# esp32_cam_rev_B.net
KiCad netlist of a schematic drawn in EAGLE
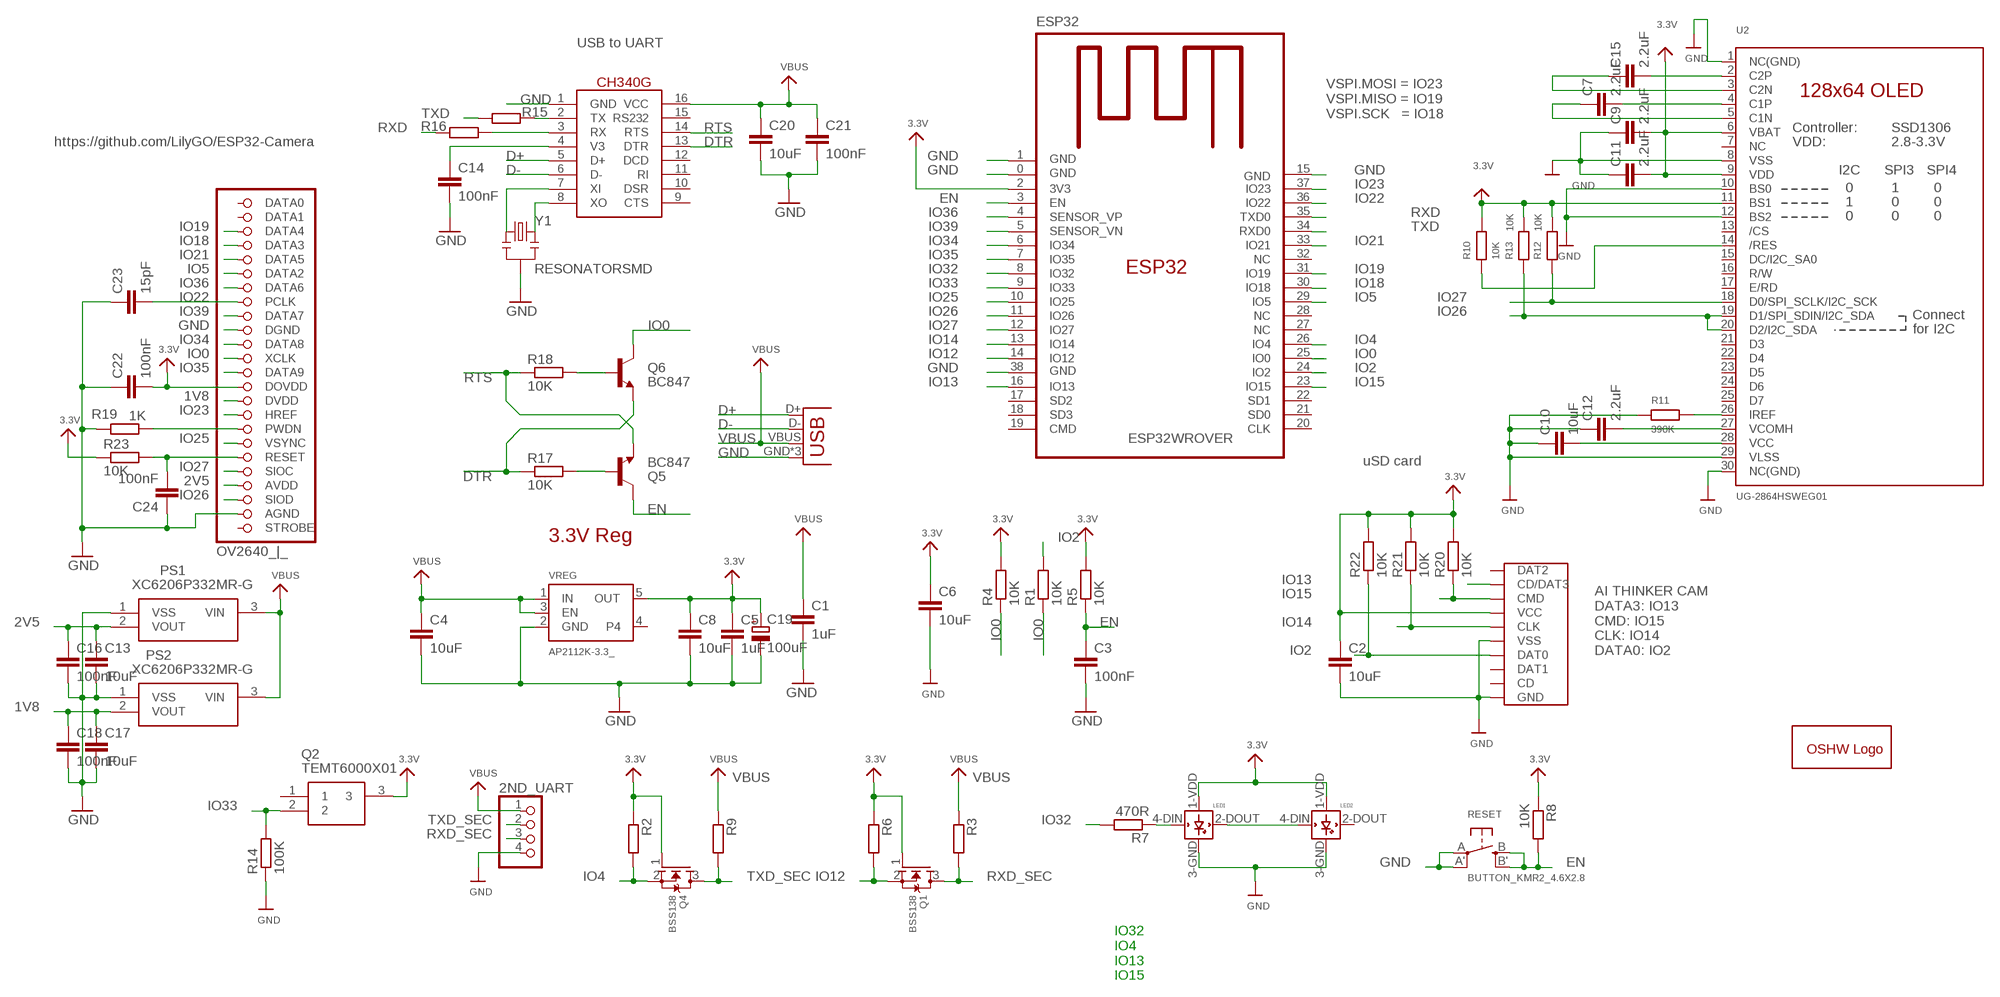
[diagram p0: schematic, sheet 1]

(export (version "E")
  (design (tool "Eeschema 10.0.6"))
  (components
    (comp (ref "2ND_UART")
      (value "JST_PH4")
      (footprint "eagle-import:JSTPH4")
      (libsource (lib "eagle-import") (part "JST_PH4"))
    )
    (comp (ref "C1")
      (value "1uF")
      (footprint "eagle-import:C0805K")
      (libsource (lib "eagle-import") (part "C-EUC0805K"))
    )
    (comp (ref "C2")
      (value "10uF")
      (footprint "eagle-import:C0805")
      (libsource (lib "eagle-import") (part "C-EUC0805"))
    )
    (comp (ref "C3")
      (value "100nF")
      (footprint "eagle-import:C0805K")
      (libsource (lib "eagle-import") (part "C-EUC0805K"))
    )
    (comp (ref "C4")
      (value "10uF")
      (footprint "eagle-import:C0805")
      (libsource (lib "eagle-import") (part "C-EUC0805"))
    )
    (comp (ref "C5")
      (value "1uF")
      (footprint "eagle-import:C0805")
      (libsource (lib "eagle-import") (part "C-EUC0805"))
    )
    (comp (ref "C6")
      (value "10uF")
      (footprint "eagle-import:C0805K")
      (libsource (lib "eagle-import") (part "C-EUC0805K"))
    )
    (comp (ref "C7")
      (value "2.2uF")
      (footprint "eagle-import:C0805")
      (libsource (lib "eagle-import") (part "C-EUC0805"))
    )
    (comp (ref "C8")
      (value "10uF")
      (footprint "eagle-import:C0805")
      (libsource (lib "eagle-import") (part "C-EUC0805"))
    )
    (comp (ref "C9")
      (value "2.2uF")
      (footprint "eagle-import:C0805")
      (libsource (lib "eagle-import") (part "C-EUC0805"))
    )
    (comp (ref "C10")
      (value "10uF")
      (footprint "eagle-import:C0805")
      (libsource (lib "eagle-import") (part "C-EUC0805"))
    )
    (comp (ref "C11")
      (value "2.2uF")
      (footprint "eagle-import:C0805")
      (libsource (lib "eagle-import") (part "C-EUC0805"))
    )
    (comp (ref "C12")
      (value "2.2uF")
      (footprint "eagle-import:C0805")
      (libsource (lib "eagle-import") (part "C-EUC0805"))
    )
    (comp (ref "C13")
      (value "10uF")
      (footprint "eagle-import:C0805")
      (libsource (lib "eagle-import") (part "C-EUC0805"))
    )
    (comp (ref "C14")
      (value "100nF")
      (footprint "eagle-import:C0805K")
      (libsource (lib "eagle-import") (part "C-EUC0805K"))
    )
    (comp (ref "C15")
      (value "2.2uF")
      (footprint "eagle-import:C0805")
      (libsource (lib "eagle-import") (part "C-EUC0805"))
    )
    (comp (ref "C16")
      (value "100nF")
      (footprint "eagle-import:C0805")
      (libsource (lib "eagle-import") (part "C-EUC0805"))
    )
    (comp (ref "C17")
      (value "10uF")
      (footprint "eagle-import:C0805")
      (libsource (lib "eagle-import") (part "C-EUC0805"))
    )
    (comp (ref "C18")
      (value "100nF")
      (footprint "eagle-import:C0805")
      (libsource (lib "eagle-import") (part "C-EUC0805"))
    )
    (comp (ref "C19")
      (value "100uF")
      (footprint "eagle-import:CT6032")
      (libsource (lib "eagle-import") (part "CPOL-EUCT6032"))
    )
    (comp (ref "C20")
      (value "10uF")
      (footprint "eagle-import:C0805")
      (libsource (lib "eagle-import") (part "C-EUC0805"))
    )
    (comp (ref "C21")
      (value "100nF")
      (footprint "eagle-import:C0805")
      (libsource (lib "eagle-import") (part "C-EUC0805"))
    )
    (comp (ref "C22")
      (value "100nF")
      (footprint "eagle-import:C0805")
      (libsource (lib "eagle-import") (part "C-EUC0805"))
    )
    (comp (ref "C23")
      (value "15pF")
      (footprint "eagle-import:C0805")
      (libsource (lib "eagle-import") (part "C-EUC0805"))
    )
    (comp (ref "C24")
      (value "100nF")
      (footprint "eagle-import:C0805")
      (libsource (lib "eagle-import") (part "C-EUC0805"))
    )
    (comp (ref "CH340G")
      (value "CH340G")
      (footprint "eagle-import:SO16")
      (libsource (lib "eagle-import") (part "CH340G"))
    )
    (comp (ref "ESP32")
      (value "ESP32WROVER")
      (footprint "eagle-import:ESP32WROVER")
      (libsource (lib "eagle-import") (part "ESP32WROVER"))
    )
    (comp (ref "FPC_CONNECTOR")
      (value "OV2640_|_")
      (footprint "eagle-import:5051102491")
      (libsource (lib "eagle-import") (part "OV2640_|_"))
    )
    (comp (ref "GOLD_ORB_SM1")
      (value "OSHWLOGO_")
      (footprint "eagle-import:OSHW_5MM_LOGO")
      (libsource (lib "eagle-import") (part "OSHWLOGO_"))
    )
    (comp (ref "LED1")
      (value "WS2812B")
      (footprint "eagle-import:WS2812B_5050")
      (libsource (lib "eagle-import") (part "WS2812B"))
    )
    (comp (ref "LED2")
      (value "WS2812B")
      (footprint "eagle-import:WS2812B_5050")
      (libsource (lib "eagle-import") (part "WS2812B"))
    )
    (comp (ref "PS1")
      (value "XC6206P332MR-G")
      (footprint "eagle-import:SOT95P280X130-3N")
      (fields (field (name "MOUSER_PART_NUMBER") "865-XC6206P332MR-G"))
      (libsource (lib "eagle-import") (part "XC6206P332MR-G"))
    )
    (comp (ref "PS2")
      (value "XC6206P332MR-G")
      (footprint "eagle-import:SOT95P280X130-3N")
      (fields (field (name "MOUSER_PART_NUMBER") "865-XC6206P332MR-G"))
      (libsource (lib "eagle-import") (part "XC6206P332MR-G"))
    )
    (comp (ref "Q1")
      (value "BSS138")
      (footprint "eagle-import:SOT95P240X110-3")
      (libsource (lib "eagle-import") (part "MOSFET_N_"))
    )
    (comp (ref "Q2")
      (value "TEMT6000X01")
      (footprint "eagle-import:TEMT6000X01")
      (fields (field (name "MOUSER_PART_NUMBER") "78-TEMT6000"))
      (libsource (lib "eagle-import") (part "TEMT6000X01"))
    )
    (comp (ref "Q4")
      (value "BSS138")
      (footprint "eagle-import:SOT95P240X110-3")
      (libsource (lib "eagle-import") (part "MOSFET_N_"))
    )
    (comp (ref "Q5")
      (value "BC847")
      (footprint "eagle-import:SOT23-3")
      (libsource (lib "eagle-import") (part "TRANSISTOR_NPNSOT23-3"))
    )
    (comp (ref "Q6")
      (value "BC847")
      (footprint "eagle-import:SOT23-3")
      (libsource (lib "eagle-import") (part "TRANSISTOR_NPNSOT23-3"))
    )
    (comp (ref "R1")
      (value "10K")
      (footprint "eagle-import:R0805")
      (libsource (lib "eagle-import") (part "R-EU_R0805"))
    )
    (comp (ref "R2")
      (value "10K")
      (footprint "eagle-import:R0805")
      (libsource (lib "eagle-import") (part "R-EU_R0805"))
    )
    (comp (ref "R3")
      (value "10K")
      (footprint "eagle-import:R0805")
      (libsource (lib "eagle-import") (part "R-EU_R0805"))
    )
    (comp (ref "R4")
      (value "10K")
      (footprint "eagle-import:R0805")
      (libsource (lib "eagle-import") (part "R-EU_R0805"))
    )
    (comp (ref "R5")
      (value "10K")
      (footprint "eagle-import:R0805")
      (libsource (lib "eagle-import") (part "R-EU_R0805"))
    )
    (comp (ref "R6")
      (value "10K")
      (footprint "eagle-import:R0805")
      (libsource (lib "eagle-import") (part "R-EU_R0805"))
    )
    (comp (ref "R7")
      (value "470R")
      (footprint "eagle-import:R0805")
      (libsource (lib "eagle-import") (part "R-EU_R0805"))
    )
    (comp (ref "R8")
      (value "10K")
      (footprint "eagle-import:R0805")
      (libsource (lib "eagle-import") (part "R-EU_R0805"))
    )
    (comp (ref "R9")
      (value "10K")
      (footprint "eagle-import:R0805")
      (libsource (lib "eagle-import") (part "R-EU_R0805"))
    )
    (comp (ref "R10")
      (value "10K")
      (footprint "eagle-import:R0805")
      (libsource (lib "eagle-import") (part "R-EU_R0805"))
    )
    (comp (ref "R11")
      (value "390K")
      (footprint "eagle-import:R0805")
      (libsource (lib "eagle-import") (part "R-EU_R0805"))
    )
    (comp (ref "R12")
      (value "10K")
      (footprint "eagle-import:R0805")
      (libsource (lib "eagle-import") (part "R-EU_R0805"))
    )
    (comp (ref "R13")
      (value "10K")
      (footprint "eagle-import:R0805")
      (libsource (lib "eagle-import") (part "R-EU_R0805"))
    )
    (comp (ref "R14")
      (value "100K")
      (footprint "eagle-import:R0805")
      (libsource (lib "eagle-import") (part "R-EU_R0805"))
    )
    (comp (ref "R15")
      (value "470R")
      (footprint "eagle-import:R0805")
      (libsource (lib "eagle-import") (part "R-EU_R0805"))
    )
    (comp (ref "R16")
      (value "470R")
      (footprint "eagle-import:R0805")
      (libsource (lib "eagle-import") (part "R-EU_R0805"))
    )
    (comp (ref "R17")
      (value "10K")
      (footprint "eagle-import:R0805")
      (libsource (lib "eagle-import") (part "R-EU_R0805"))
    )
    (comp (ref "R18")
      (value "10K")
      (footprint "eagle-import:R0805")
      (libsource (lib "eagle-import") (part "R-EU_R0805"))
    )
    (comp (ref "R19")
      (value "1K")
      (footprint "eagle-import:R0805")
      (libsource (lib "eagle-import") (part "R-EU_R0805"))
    )
    (comp (ref "R20")
      (value "10K")
      (footprint "eagle-import:R0805")
      (libsource (lib "eagle-import") (part "R-EU_R0805"))
    )
    (comp (ref "R21")
      (value "10K")
      (footprint "eagle-import:R0805")
      (libsource (lib "eagle-import") (part "R-EU_R0805"))
    )
    (comp (ref "R22")
      (value "10K")
      (footprint "eagle-import:R0805")
      (libsource (lib "eagle-import") (part "R-EU_R0805"))
    )
    (comp (ref "R23")
      (value "10K")
      (footprint "eagle-import:R0805")
      (libsource (lib "eagle-import") (part "R-EU_R0805"))
    )
    (comp (ref "RESET")
      (value "BUTTON_KMR2_4.6X2.8")
      (footprint "eagle-import:BUTTON_KMR2_4.6X2.8")
      (libsource (lib "eagle-import") (part "BUTTON_KMR2_4.6X2.8"))
    )
    (comp (ref "SD_CARD")
      (value "MICRO_SD_CARD_")
      (footprint "eagle-import:TFP09-2--12B")
      (libsource (lib "eagle-import") (part "MICRO_SD_CARD_"))
    )
    (comp (ref "U2")
      (value "UG-2864HSWEG01")
      (footprint "eagle-import:UG-2864HSWEG01_1.3_WRAPAROUND_MIRRORED")
      (libsource (lib "eagle-import") (part "DISP_OLED_UG-2864HSWEG01_"))
    )
    (comp (ref "USB")
      (value "USB_MICRO_ATTEND_")
      (footprint "eagle-import:USB_MICRO")
      (libsource (lib "eagle-import") (part "USB_MICRO_ATTEND_"))
    )
    (comp (ref "VREG")
      (value "AP2112K-3.3_")
      (footprint "eagle-import:SOT95P290X120-5")
      (libsource (lib "eagle-import") (part "AP2112K-3.3_"))
    )
    (comp (ref "Y1")
      (value "RESONATORSMD")
      (footprint "eagle-import:RESONATOR-SMD")
      (libsource (lib "eagle-import") (part "RESONATORSMD"))
    )
  )
  (nets
    (net (code "1") (name "/1V8") (class "Default")
      (node (ref "C17") (pin "1") (pinfunction "1_1") (pintype "passive"))
      (node (ref "C18") (pin "1") (pinfunction "1_1") (pintype "passive"))
      (node (ref "FPC_CONNECTOR") (pin "15") (pinfunction "DVDD_15") (pintype "passive"))
      (node (ref "PS2") (pin "2") (pinfunction "VOUT_2") (pintype "power_in"))
    )
    (net (code "2") (name "/2V5") (class "Default")
      (node (ref "C13") (pin "1") (pinfunction "1_1") (pintype "passive"))
      (node (ref "C16") (pin "1") (pinfunction "1_1") (pintype "passive"))
      (node (ref "FPC_CONNECTOR") (pin "21") (pinfunction "AVDD_21") (pintype "passive"))
      (node (ref "PS1") (pin "2") (pinfunction "VOUT_2") (pintype "power_in"))
    )
    (net (code "3") (name "/D+") (class "Default")
      (node (ref "CH340G") (pin "5") (pinfunction "D+_5") (pintype "bidirectional"))
      (node (ref "USB") (pin "D+") (pinfunction "D+_D+") (pintype "bidirectional"))
    )
    (net (code "4") (name "/D-") (class "Default")
      (node (ref "CH340G") (pin "6") (pinfunction "D-_6") (pintype "bidirectional"))
      (node (ref "USB") (pin "D-") (pinfunction "D-_D-") (pintype "bidirectional"))
    )
    (net (code "5") (name "/DTR") (class "Default")
      (node (ref "CH340G") (pin "13") (pinfunction "DTR_13") (pintype "bidirectional"))
      (node (ref "Q6") (pin "2") (pinfunction "E_2") (pintype "passive"))
      (node (ref "R17") (pin "1") (pinfunction "1_1") (pintype "passive"))
    )
    (net (code "6") (name "/EN") (class "Default")
      (node (ref "C3") (pin "1") (pinfunction "1_1") (pintype "passive"))
      (node (ref "ESP32") (pin "3") (pinfunction "EN_3") (pintype "bidirectional"))
      (node (ref "Q5") (pin "3") (pinfunction "C_3") (pintype "passive"))
      (node (ref "R5") (pin "1") (pinfunction "1_1") (pintype "passive"))
      (node (ref "R8") (pin "2") (pinfunction "2_2") (pintype "passive"))
      (node (ref "RESET") (pin "B") (pinfunction "S_B") (pintype "passive"))
      (node (ref "RESET") (pin "B'") (pinfunction "S1_B'") (pintype "passive"))
    )
    (net (code "7") (name "/IO0") (class "Default")
      (node (ref "ESP32") (pin "25") (pinfunction "IO0_25") (pintype "bidirectional"))
      (node (ref "FPC_CONNECTOR") (pin "12") (pinfunction "XCLK_12") (pintype "passive"))
      (node (ref "Q6") (pin "3") (pinfunction "C_3") (pintype "passive"))
      (node (ref "R1") (pin "1") (pinfunction "1_1") (pintype "passive"))
      (node (ref "R4") (pin "1") (pinfunction "1_1") (pintype "passive"))
    )
    (net (code "8") (name "/IO2") (class "Default")
      (node (ref "ESP32") (pin "24") (pinfunction "IO2_24") (pintype "bidirectional"))
      (node (ref "R1") (pin "2") (pinfunction "2_2") (pintype "passive"))
      (node (ref "R22") (pin "1") (pinfunction "1_1") (pintype "passive"))
      (node (ref "SD_CARD") (pin "DAT0") (pinfunction "DAT0_DAT0") (pintype "bidirectional"))
    )
    (net (code "9") (name "/IO4") (class "Default")
      (node (ref "ESP32") (pin "26") (pinfunction "IO4_26") (pintype "bidirectional"))
      (node (ref "Q4") (pin "2") (pinfunction "S_2") (pintype "bidirectional"))
      (node (ref "R2") (pin "2") (pinfunction "2_2") (pintype "passive"))
    )
    (net (code "10") (name "/IO5") (class "Default")
      (node (ref "ESP32") (pin "29") (pinfunction "IO5_29") (pintype "bidirectional"))
      (node (ref "FPC_CONNECTOR") (pin "6") (pinfunction "DATA2_6") (pintype "passive"))
    )
    (net (code "11") (name "/IO12") (class "Default")
      (node (ref "ESP32") (pin "14") (pinfunction "IO12_14") (pintype "bidirectional"))
      (node (ref "Q1") (pin "2") (pinfunction "S_2") (pintype "bidirectional"))
      (node (ref "R6") (pin "2") (pinfunction "2_2") (pintype "passive"))
    )
    (net (code "12") (name "/IO13") (class "Default")
      (node (ref "ESP32") (pin "16") (pinfunction "IO13_16") (pintype "bidirectional"))
      (node (ref "SD_CARD") (pin "CD/DAT3") (pinfunction "CD/DAT3_CD/DAT3") (pintype "bidirectional"))
    )
    (net (code "13") (name "/IO14") (class "Default")
      (node (ref "ESP32") (pin "13") (pinfunction "IO14_13") (pintype "bidirectional"))
      (node (ref "R21") (pin "1") (pinfunction "1_1") (pintype "passive"))
      (node (ref "SD_CARD") (pin "CLK") (pinfunction "CLK_CLK") (pintype "bidirectional"))
    )
    (net (code "14") (name "/IO15") (class "Default")
      (node (ref "ESP32") (pin "23") (pinfunction "IO15_23") (pintype "bidirectional"))
      (node (ref "R20") (pin "1") (pinfunction "1_1") (pintype "passive"))
      (node (ref "SD_CARD") (pin "CMD") (pinfunction "CMD_CMD") (pintype "bidirectional"))
    )
    (net (code "15") (name "/IO18") (class "Default")
      (node (ref "ESP32") (pin "30") (pinfunction "IO18_30") (pintype "bidirectional"))
      (node (ref "FPC_CONNECTOR") (pin "4") (pinfunction "DATA3_4") (pintype "passive"))
    )
    (net (code "16") (name "/IO19") (class "Default")
      (node (ref "ESP32") (pin "31") (pinfunction "IO19_31") (pintype "bidirectional"))
      (node (ref "FPC_CONNECTOR") (pin "3") (pinfunction "DATA4_3") (pintype "passive"))
    )
    (net (code "17") (name "/IO21") (class "Default")
      (node (ref "ESP32") (pin "33") (pinfunction "IO21_33") (pintype "bidirectional"))
      (node (ref "FPC_CONNECTOR") (pin "5") (pinfunction "DATA5_5") (pintype "passive"))
    )
    (net (code "18") (name "/IO22") (class "Default")
      (node (ref "C23") (pin "2") (pinfunction "2_2") (pintype "passive"))
      (node (ref "ESP32") (pin "36") (pinfunction "IO22_36") (pintype "bidirectional"))
      (node (ref "FPC_CONNECTOR") (pin "8") (pinfunction "PCLK_8") (pintype "passive"))
    )
    (net (code "19") (name "/IO23") (class "Default")
      (node (ref "ESP32") (pin "37") (pinfunction "IO23_37") (pintype "bidirectional"))
      (node (ref "FPC_CONNECTOR") (pin "16") (pinfunction "HREF_16") (pintype "passive"))
    )
    (net (code "20") (name "/IO25") (class "Default")
      (node (ref "ESP32") (pin "10") (pinfunction "IO25_10") (pintype "bidirectional"))
      (node (ref "FPC_CONNECTOR") (pin "18") (pinfunction "VSYNC_18") (pintype "passive"))
    )
    (net (code "21") (name "/IO26") (class "Default")
      (node (ref "ESP32") (pin "11") (pinfunction "IO26_11") (pintype "bidirectional"))
      (node (ref "FPC_CONNECTOR") (pin "22") (pinfunction "SIOD_22") (pintype "passive"))
      (node (ref "R13") (pin "1") (pinfunction "1_1") (pintype "passive"))
      (node (ref "U2") (pin "19") (pinfunction "D1/SPI_SDIN/I2C_SDA_19") (pintype "bidirectional"))
      (node (ref "U2") (pin "20") (pinfunction "D2/I2C_SDA_20") (pintype "bidirectional"))
    )
    (net (code "22") (name "/IO27") (class "Default")
      (node (ref "ESP32") (pin "12") (pinfunction "IO27_12") (pintype "bidirectional"))
      (node (ref "FPC_CONNECTOR") (pin "20") (pinfunction "SIOC_20") (pintype "passive"))
      (node (ref "R12") (pin "1") (pinfunction "1_1") (pintype "passive"))
      (node (ref "U2") (pin "18") (pinfunction "D0/SPI_SCLK/I2C_SCK_18") (pintype "bidirectional"))
    )
    (net (code "23") (name "/IO32") (class "Default")
      (node (ref "ESP32") (pin "8") (pinfunction "IO32_8") (pintype "bidirectional"))
      (node (ref "R7") (pin "2") (pinfunction "2_2") (pintype "passive"))
    )
    (net (code "24") (name "/IO33") (class "Default")
      (node (ref "ESP32") (pin "9") (pinfunction "IO33_9") (pintype "bidirectional"))
      (node (ref "Q2") (pin "2") (pinfunction "2_2") (pintype "bidirectional"))
      (node (ref "R14") (pin "2") (pinfunction "2_2") (pintype "passive"))
    )
    (net (code "25") (name "/IO34") (class "Default")
      (node (ref "ESP32") (pin "6") (pinfunction "IO34_6") (pintype "bidirectional"))
      (node (ref "FPC_CONNECTOR") (pin "11") (pinfunction "DATA8_11") (pintype "passive"))
    )
    (net (code "26") (name "/IO35") (class "Default")
      (node (ref "ESP32") (pin "7") (pinfunction "IO35_7") (pintype "bidirectional"))
      (node (ref "FPC_CONNECTOR") (pin "13") (pinfunction "DATA9_13") (pintype "passive"))
    )
    (net (code "27") (name "/IO36") (class "Default")
      (node (ref "ESP32") (pin "4") (pinfunction "SENSOR_VP_4") (pintype "bidirectional"))
      (node (ref "FPC_CONNECTOR") (pin "7") (pinfunction "DATA6_7") (pintype "passive"))
    )
    (net (code "28") (name "/IO39") (class "Default")
      (node (ref "ESP32") (pin "5") (pinfunction "SENSOR_VN_5") (pintype "bidirectional"))
      (node (ref "FPC_CONNECTOR") (pin "9") (pinfunction "DATA7_9") (pintype "passive"))
    )
    (net (code "29") (name "/RTS") (class "Default")
      (node (ref "CH340G") (pin "14") (pinfunction "RTS_14") (pintype "bidirectional"))
      (node (ref "Q5") (pin "2") (pinfunction "E_2") (pintype "passive"))
      (node (ref "R18") (pin "1") (pinfunction "1_1") (pintype "passive"))
    )
    (net (code "30") (name "/RXD") (class "Default")
      (node (ref "ESP32") (pin "35") (pinfunction "TXD0_35") (pintype "bidirectional"))
      (node (ref "R16") (pin "2") (pinfunction "2_2") (pintype "passive"))
    )
    (net (code "31") (name "/RXD_SEC") (class "Default")
      (node (ref "2ND_UART") (pin "3") (pinfunction "3_3") (pintype "passive"))
      (node (ref "Q1") (pin "3") (pinfunction "D_3") (pintype "bidirectional"))
      (node (ref "R3") (pin "2") (pinfunction "2_2") (pintype "passive"))
    )
    (net (code "32") (name "/TXD") (class "Default")
      (node (ref "ESP32") (pin "34") (pinfunction "RXD0_34") (pintype "bidirectional"))
      (node (ref "R15") (pin "2") (pinfunction "2_2") (pintype "passive"))
    )
    (net (code "33") (name "/TXD_SEC") (class "Default")
      (node (ref "2ND_UART") (pin "2") (pinfunction "2_2") (pintype "passive"))
      (node (ref "Q4") (pin "3") (pinfunction "D_3") (pintype "bidirectional"))
      (node (ref "R9") (pin "2") (pinfunction "2_2") (pintype "passive"))
    )
    (net (code "34") (name "3.3V") (class "Default")
      (node (ref "C11") (pin "2") (pinfunction "2_2") (pintype "passive"))
      (node (ref "C19") (pin "+") (pinfunction "+_+") (pintype "passive"))
      (node (ref "C2") (pin "1") (pinfunction "1_1") (pintype "passive"))
      (node (ref "C22") (pin "2") (pinfunction "2_2") (pintype "passive"))
      (node (ref "C5") (pin "1") (pinfunction "1_1") (pintype "passive"))
      (node (ref "C6") (pin "1") (pinfunction "1_1") (pintype "passive"))
      (node (ref "C8") (pin "1") (pinfunction "1_1") (pintype "passive"))
      (node (ref "C9") (pin "2") (pinfunction "2_2") (pintype "passive"))
      (node (ref "ESP32") (pin "2") (pinfunction "3V3_2") (pintype "power_in"))
      (node (ref "FPC_CONNECTOR") (pin "14") (pinfunction "DOVDD_14") (pintype "passive"))
      (node (ref "LED1") (pin "1-VDD") (pinfunction "VDD_1-VDD") (pintype "power_in"))
      (node (ref "LED2") (pin "1-VDD") (pinfunction "VDD_1-VDD") (pintype "power_in"))
      (node (ref "Q1") (pin "1") (pinfunction "G_1") (pintype "bidirectional"))
      (node (ref "Q2") (pin "3") (pinfunction "3_3") (pintype "bidirectional"))
      (node (ref "Q4") (pin "1") (pinfunction "G_1") (pintype "bidirectional"))
      (node (ref "R10") (pin "2") (pinfunction "2_2") (pintype "passive"))
      (node (ref "R12") (pin "2") (pinfunction "2_2") (pintype "passive"))
      (node (ref "R13") (pin "2") (pinfunction "2_2") (pintype "passive"))
      (node (ref "R2") (pin "1") (pinfunction "1_1") (pintype "passive"))
      (node (ref "R20") (pin "2") (pinfunction "2_2") (pintype "passive"))
      (node (ref "R21") (pin "2") (pinfunction "2_2") (pintype "passive"))
      (node (ref "R22") (pin "2") (pinfunction "2_2") (pintype "passive"))
      (node (ref "R23") (pin "1") (pinfunction "1_1") (pintype "passive"))
      (node (ref "R4") (pin "2") (pinfunction "2_2") (pintype "passive"))
      (node (ref "R5") (pin "2") (pinfunction "2_2") (pintype "passive"))
      (node (ref "R6") (pin "1") (pinfunction "1_1") (pintype "passive"))
      (node (ref "R8") (pin "1") (pinfunction "1_1") (pintype "passive"))
      (node (ref "SD_CARD") (pin "VCC") (pinfunction "VCC_VCC") (pintype "bidirectional"))
      (node (ref "U2") (pin "11") (pinfunction "BS1_11") (pintype "input"))
      (node (ref "U2") (pin "6") (pinfunction "VBAT_6") (pintype "input"))
      (node (ref "U2") (pin "9") (pinfunction "VDD_9") (pintype "power_in"))
      (node (ref "VREG") (pin "5") (pinfunction "OUT_5") (pintype "bidirectional"))
    )
    (net (code "35") (name "GND") (class "Default")
      (node (ref "2ND_UART") (pin "4") (pinfunction "4_4") (pintype "passive"))
      (node (ref "C1") (pin "2") (pinfunction "2_2") (pintype "passive"))
      (node (ref "C10") (pin "1") (pinfunction "1_1") (pintype "passive"))
      (node (ref "C11") (pin "1") (pinfunction "1_1") (pintype "passive"))
      (node (ref "C12") (pin "1") (pinfunction "1_1") (pintype "passive"))
      (node (ref "C13") (pin "2") (pinfunction "2_2") (pintype "passive"))
      (node (ref "C14") (pin "2") (pinfunction "2_2") (pintype "passive"))
      (node (ref "C16") (pin "2") (pinfunction "2_2") (pintype "passive"))
      (node (ref "C17") (pin "2") (pinfunction "2_2") (pintype "passive"))
      (node (ref "C18") (pin "2") (pinfunction "2_2") (pintype "passive"))
      (node (ref "C19") (pin "-") (pinfunction "-_-") (pintype "passive"))
      (node (ref "C2") (pin "2") (pinfunction "2_2") (pintype "passive"))
      (node (ref "C20") (pin "2") (pinfunction "2_2") (pintype "passive"))
      (node (ref "C21") (pin "2") (pinfunction "2_2") (pintype "passive"))
      (node (ref "C22") (pin "1") (pinfunction "1_1") (pintype "passive"))
      (node (ref "C23") (pin "1") (pinfunction "1_1") (pintype "passive"))
      (node (ref "C24") (pin "1") (pinfunction "1_1") (pintype "passive"))
      (node (ref "C3") (pin "2") (pinfunction "2_2") (pintype "passive"))
      (node (ref "C4") (pin "2") (pinfunction "2_2") (pintype "passive"))
      (node (ref "C5") (pin "2") (pinfunction "2_2") (pintype "passive"))
      (node (ref "C6") (pin "2") (pinfunction "2_2") (pintype "passive"))
      (node (ref "C8") (pin "2") (pinfunction "2_2") (pintype "passive"))
      (node (ref "C9") (pin "1") (pinfunction "1_1") (pintype "passive"))
      (node (ref "CH340G") (pin "1") (pinfunction "GND_1") (pintype "bidirectional"))
      (node (ref "ESP32") (pin "0") (pinfunction "GND_0") (pintype "power_in"))
      (node (ref "ESP32") (pin "1") (pinfunction "GND_1") (pintype "power_in"))
      (node (ref "ESP32") (pin "15") (pinfunction "GND_15") (pintype "power_in"))
      (node (ref "ESP32") (pin "38") (pinfunction "GND_38") (pintype "power_in"))
      (node (ref "FPC_CONNECTOR") (pin "10") (pinfunction "DGND_10") (pintype "passive"))
      (node (ref "FPC_CONNECTOR") (pin "23") (pinfunction "AGND_23") (pintype "passive"))
      (node (ref "LED1") (pin "3-GND") (pinfunction "GND_3-GND") (pintype "power_in"))
      (node (ref "LED2") (pin "3-GND") (pinfunction "GND_3-GND") (pintype "power_in"))
      (node (ref "PS1") (pin "1") (pinfunction "VSS_1") (pintype "power_in"))
      (node (ref "PS2") (pin "1") (pinfunction "VSS_1") (pintype "power_in"))
      (node (ref "R11") (pin "1") (pinfunction "1_1") (pintype "passive"))
      (node (ref "R14") (pin "1") (pinfunction "1_1") (pintype "passive"))
      (node (ref "R19") (pin "2") (pinfunction "2_2") (pintype "passive"))
      (node (ref "RESET") (pin "A") (pinfunction "P_A") (pintype "passive"))
      (node (ref "RESET") (pin "A'") (pinfunction "P1_A'") (pintype "passive"))
      (node (ref "SD_CARD") (pin "GND") (pinfunction "GND_GND") (pintype "bidirectional"))
      (node (ref "SD_CARD") (pin "GND@1") (pinfunction "GND_GND@1") (pintype "bidirectional"))
      (node (ref "SD_CARD") (pin "GND@2") (pinfunction "GND_GND@2") (pintype "bidirectional"))
      (node (ref "SD_CARD") (pin "GND@3") (pinfunction "VSS_GND@3") (pintype "bidirectional"))
      (node (ref "SD_CARD") (pin "VSS") (pinfunction "GND_VSS") (pintype "bidirectional"))
      (node (ref "U2") (pin "1") (pinfunction "NC(GND)_1") (pintype "input"))
      (node (ref "U2") (pin "10") (pinfunction "BS0_10") (pintype "input"))
      (node (ref "U2") (pin "12") (pinfunction "BS2_12") (pintype "input"))
      (node (ref "U2") (pin "29") (pinfunction "VLSS_29") (pintype "power_in"))
      (node (ref "U2") (pin "30") (pinfunction "NC(GND)_30") (pintype "input"))
      (node (ref "U2") (pin "8") (pinfunction "VSS_8") (pintype "power_in"))
      (node (ref "USB") (pin "GND") (pinfunction "GND_GND") (pintype "bidirectional"))
      (node (ref "USB") (pin "GND@2") (pinfunction "GND_GND@2") (pintype "bidirectional"))
      (node (ref "USB") (pin "GND@3") (pinfunction "GND_GND@3") (pintype "bidirectional"))
      (node (ref "VREG") (pin "2") (pinfunction "GND_2") (pintype "bidirectional"))
      (node (ref "Y1") (pin "2") (pinfunction "2_2") (pintype "passive"))
    )
    (net (code "36") (name "Net-(CH340G-RX)") (class "Default")
      (node (ref "CH340G") (pin "3") (pinfunction "RX_3") (pintype "bidirectional"))
      (node (ref "R16") (pin "1") (pinfunction "1_1") (pintype "passive"))
    )
    (net (code "37") (name "Net-(CH340G-TX)") (class "Default")
      (node (ref "CH340G") (pin "2") (pinfunction "TX_2") (pintype "bidirectional"))
      (node (ref "R15") (pin "1") (pinfunction "1_1") (pintype "passive"))
    )
    (net (code "38") (name "Net-(CH340G-V3)") (class "Default")
      (node (ref "C14") (pin "1") (pinfunction "1_1") (pintype "passive"))
      (node (ref "CH340G") (pin "4") (pinfunction "V3_4") (pintype "bidirectional"))
    )
    (net (code "39") (name "Net-(CH340G-XI)") (class "Default")
      (node (ref "CH340G") (pin "7") (pinfunction "XI_7") (pintype "bidirectional"))
      (node (ref "Y1") (pin "1") (pinfunction "1_1") (pintype "passive"))
    )
    (net (code "40") (name "Net-(CH340G-XO)") (class "Default")
      (node (ref "CH340G") (pin "8") (pinfunction "XO_8") (pintype "bidirectional"))
      (node (ref "Y1") (pin "3") (pinfunction "3_3") (pintype "passive"))
    )
    (net (code "41") (name "Net-(FPC_CONNECTOR-PWDN)") (class "Default")
      (node (ref "FPC_CONNECTOR") (pin "17") (pinfunction "PWDN_17") (pintype "passive"))
      (node (ref "R19") (pin "1") (pinfunction "1_1") (pintype "passive"))
    )
    (net (code "42") (name "Net-(FPC_CONNECTOR-RESET)") (class "Default")
      (node (ref "C24") (pin "2") (pinfunction "2_2") (pintype "passive"))
      (node (ref "FPC_CONNECTOR") (pin "19") (pinfunction "RESET_19") (pintype "passive"))
      (node (ref "R23") (pin "2") (pinfunction "2_2") (pintype "passive"))
    )
    (net (code "43") (name "Net-(LED1-DIN)") (class "Default")
      (node (ref "LED1") (pin "4-DIN") (pinfunction "DIN_4-DIN") (pintype "input"))
      (node (ref "R7") (pin "1") (pinfunction "1_1") (pintype "passive"))
    )
    (net (code "44") (name "Net-(LED1-DOUT)") (class "Default")
      (node (ref "LED1") (pin "2-DOUT") (pinfunction "DOUT_2-DOUT") (pintype "output"))
      (node (ref "LED2") (pin "4-DIN") (pinfunction "DIN_4-DIN") (pintype "input"))
    )
    (net (code "45") (name "Net-(Q5-B)") (class "Default")
      (node (ref "Q5") (pin "1") (pinfunction "B_1") (pintype "passive"))
      (node (ref "R17") (pin "2") (pinfunction "2_2") (pintype "passive"))
    )
    (net (code "46") (name "Net-(Q6-B)") (class "Default")
      (node (ref "Q6") (pin "1") (pinfunction "B_1") (pintype "passive"))
      (node (ref "R18") (pin "2") (pinfunction "2_2") (pintype "passive"))
    )
    (net (code "47") (name "Net-(U2-C1N)") (class "Default")
      (node (ref "C7") (pin "1") (pinfunction "1_1") (pintype "passive"))
      (node (ref "U2") (pin "5") (pinfunction "C1N_5") (pintype "input"))
    )
    (net (code "48") (name "Net-(U2-C1P)") (class "Default")
      (node (ref "C7") (pin "2") (pinfunction "2_2") (pintype "passive"))
      (node (ref "U2") (pin "4") (pinfunction "C1P_4") (pintype "input"))
    )
    (net (code "49") (name "Net-(U2-C2N)") (class "Default")
      (node (ref "C15") (pin "1") (pinfunction "1_1") (pintype "passive"))
      (node (ref "U2") (pin "3") (pinfunction "C2N_3") (pintype "input"))
    )
    (net (code "50") (name "Net-(U2-C2P)") (class "Default")
      (node (ref "C15") (pin "2") (pinfunction "2_2") (pintype "passive"))
      (node (ref "U2") (pin "2") (pinfunction "C2P_2") (pintype "input"))
    )
    (net (code "51") (name "Net-(U2-IREF)") (class "Default")
      (node (ref "R11") (pin "2") (pinfunction "2_2") (pintype "passive"))
      (node (ref "U2") (pin "26") (pinfunction "IREF_26") (pintype "input"))
    )
    (net (code "52") (name "Net-(U2-VCC)") (class "Default")
      (node (ref "C10") (pin "2") (pinfunction "2_2") (pintype "passive"))
      (node (ref "U2") (pin "28") (pinfunction "VCC_28") (pintype "power_in"))
    )
    (net (code "53") (name "Net-(U2-VCOMH)") (class "Default")
      (node (ref "C12") (pin "2") (pinfunction "2_2") (pintype "passive"))
      (node (ref "U2") (pin "27") (pinfunction "VCOMH_27") (pintype "output"))
    )
    (net (code "54") (name "Net-(U2-{slash}RES)") (class "Default")
      (node (ref "R10") (pin "1") (pinfunction "1_1") (pintype "passive"))
      (node (ref "U2") (pin "14") (pinfunction "/RES_14") (pintype "input"))
    )
    (net (code "55") (name "VBUS") (class "Default")
      (node (ref "2ND_UART") (pin "1") (pinfunction "1_1") (pintype "passive"))
      (node (ref "C1") (pin "1") (pinfunction "1_1") (pintype "passive"))
      (node (ref "C20") (pin "1") (pinfunction "1_1") (pintype "passive"))
      (node (ref "C21") (pin "1") (pinfunction "1_1") (pintype "passive"))
      (node (ref "C4") (pin "1") (pinfunction "1_1") (pintype "passive"))
      (node (ref "CH340G") (pin "16") (pinfunction "VCC_16") (pintype "bidirectional"))
      (node (ref "PS1") (pin "3") (pinfunction "VIN_3") (pintype "power_in"))
      (node (ref "PS2") (pin "3") (pinfunction "VIN_3") (pintype "power_in"))
      (node (ref "R3") (pin "1") (pinfunction "1_1") (pintype "passive"))
      (node (ref "R9") (pin "1") (pinfunction "1_1") (pintype "passive"))
      (node (ref "USB") (pin "VBUS") (pinfunction "VBUS_VBUS") (pintype "bidirectional"))
      (node (ref "VREG") (pin "1") (pinfunction "IN_1") (pintype "bidirectional"))
      (node (ref "VREG") (pin "3") (pinfunction "EN_3") (pintype "bidirectional"))
    )
    (net (code "56") (name "unconnected-(CH340G-CTS-Pad9)") (class "Default")
      (node (ref "CH340G") (pin "9") (pinfunction "CTS_9") (pintype "bidirectional"))
    )
    (net (code "57") (name "unconnected-(CH340G-DCD-Pad12)") (class "Default")
      (node (ref "CH340G") (pin "12") (pinfunction "DCD_12") (pintype "bidirectional"))
    )
    (net (code "58") (name "unconnected-(CH340G-DSR-Pad10)") (class "Default")
      (node (ref "CH340G") (pin "10") (pinfunction "DSR_10") (pintype "bidirectional"))
    )
    (net (code "59") (name "unconnected-(CH340G-RI-Pad11)") (class "Default")
      (node (ref "CH340G") (pin "11") (pinfunction "RI_11") (pintype "bidirectional"))
    )
    (net (code "60") (name "unconnected-(CH340G-RS232-Pad15)") (class "Default")
      (node (ref "CH340G") (pin "15") (pinfunction "RS232_15") (pintype "bidirectional"))
    )
    (net (code "61") (name "unconnected-(ESP32-CLK-Pad20)") (class "Default")
      (node (ref "ESP32") (pin "20") (pinfunction "CLK_20") (pintype "bidirectional"))
    )
    (net (code "62") (name "unconnected-(ESP32-CMD-Pad19)") (class "Default")
      (node (ref "ESP32") (pin "19") (pinfunction "CMD_19") (pintype "bidirectional"))
    )
    (net (code "63") (name "unconnected-(ESP32-NC-Pad27)") (class "Default")
      (node (ref "ESP32") (pin "27") (pinfunction "NC_27") (pintype "bidirectional"))
    )
    (net (code "64") (name "unconnected-(ESP32-NC-Pad28)") (class "Default")
      (node (ref "ESP32") (pin "28") (pinfunction "NC_28") (pintype "bidirectional"))
    )
    (net (code "65") (name "unconnected-(ESP32-NC-Pad32)") (class "Default")
      (node (ref "ESP32") (pin "32") (pinfunction "NC_32") (pintype "bidirectional"))
    )
    (net (code "66") (name "unconnected-(ESP32-SD0-Pad21)") (class "Default")
      (node (ref "ESP32") (pin "21") (pinfunction "SD0_21") (pintype "bidirectional"))
    )
    (net (code "67") (name "unconnected-(ESP32-SD1-Pad22)") (class "Default")
      (node (ref "ESP32") (pin "22") (pinfunction "SD1_22") (pintype "bidirectional"))
    )
    (net (code "68") (name "unconnected-(ESP32-SD2-Pad17)") (class "Default")
      (node (ref "ESP32") (pin "17") (pinfunction "SD2_17") (pintype "bidirectional"))
    )
    (net (code "69") (name "unconnected-(ESP32-SD3-Pad18)") (class "Default")
      (node (ref "ESP32") (pin "18") (pinfunction "SD3_18") (pintype "bidirectional"))
    )
    (net (code "70") (name "unconnected-(FPC_CONNECTOR-DATA0-Pad1)") (class "Default")
      (node (ref "FPC_CONNECTOR") (pin "1") (pinfunction "DATA0_1") (pintype "passive"))
    )
    (net (code "71") (name "unconnected-(FPC_CONNECTOR-DATA1-Pad2)") (class "Default")
      (node (ref "FPC_CONNECTOR") (pin "2") (pinfunction "DATA1_2") (pintype "passive"))
    )
    (net (code "72") (name "unconnected-(FPC_CONNECTOR-STROBE-Pad24)") (class "Default")
      (node (ref "FPC_CONNECTOR") (pin "24") (pinfunction "STROBE_24") (pintype "passive"))
    )
    (net (code "73") (name "unconnected-(LED2-DOUT-Pad2-DOUT)") (class "Default")
      (node (ref "LED2") (pin "2-DOUT") (pinfunction "DOUT_2-DOUT") (pintype "output"))
    )
    (net (code "74") (name "unconnected-(Q2-Pad1)") (class "Default")
      (node (ref "Q2") (pin "1") (pinfunction "1_1") (pintype "bidirectional"))
    )
    (net (code "75") (name "unconnected-(SD_CARD-PadCD)") (class "Default")
      (node (ref "SD_CARD") (pin "CD") (pinfunction "CD_CD") (pintype "bidirectional"))
    )
    (net (code "76") (name "unconnected-(SD_CARD-PadDAT1)") (class "Default")
      (node (ref "SD_CARD") (pin "DAT1") (pinfunction "DAT1_DAT1") (pintype "bidirectional"))
    )
    (net (code "77") (name "unconnected-(SD_CARD-PadDAT2)") (class "Default")
      (node (ref "SD_CARD") (pin "DAT2") (pinfunction "DAT2_DAT2") (pintype "bidirectional"))
    )
    (net (code "78") (name "unconnected-(U2-D3-Pad21)") (class "Default")
      (node (ref "U2") (pin "21") (pinfunction "D3_21") (pintype "bidirectional"))
    )
    (net (code "79") (name "unconnected-(U2-D4-Pad22)") (class "Default")
      (node (ref "U2") (pin "22") (pinfunction "D4_22") (pintype "bidirectional"))
    )
    (net (code "80") (name "unconnected-(U2-D5-Pad23)") (class "Default")
      (node (ref "U2") (pin "23") (pinfunction "D5_23") (pintype "bidirectional"))
    )
    (net (code "81") (name "unconnected-(U2-D6-Pad24)") (class "Default")
      (node (ref "U2") (pin "24") (pinfunction "D6_24") (pintype "bidirectional"))
    )
    (net (code "82") (name "unconnected-(U2-D7-Pad25)") (class "Default")
      (node (ref "U2") (pin "25") (pinfunction "D7_25") (pintype "bidirectional"))
    )
    (net (code "83") (name "unconnected-(U2-DC{slash}I2C_SA0-Pad15)") (class "Default")
      (node (ref "U2") (pin "15") (pinfunction "DC/I2C_SA0_15") (pintype "input"))
    )
    (net (code "84") (name "unconnected-(U2-E{slash}RD-Pad17)") (class "Default")
      (node (ref "U2") (pin "17") (pinfunction "E/RD_17") (pintype "input"))
    )
    (net (code "85") (name "unconnected-(U2-NC-Pad7)") (class "Default")
      (node (ref "U2") (pin "7") (pinfunction "NC_7") (pintype "no_connect"))
    )
    (net (code "86") (name "unconnected-(U2-R{slash}W-Pad16)") (class "Default")
      (node (ref "U2") (pin "16") (pinfunction "R/W_16") (pintype "input"))
    )
    (net (code "87") (name "unconnected-(U2-{slash}CS-Pad13)") (class "Default")
      (node (ref "U2") (pin "13") (pinfunction "/CS_13") (pintype "input"))
    )
    (net (code "88") (name "unconnected-(VREG-P4-Pad4)") (class "Default")
      (node (ref "VREG") (pin "4") (pinfunction "P4_4") (pintype "bidirectional"))
    )
  )
)
